# RoBeast_Power_Switching.net
KiCad netlist of a schematic drawn in Altium Designer
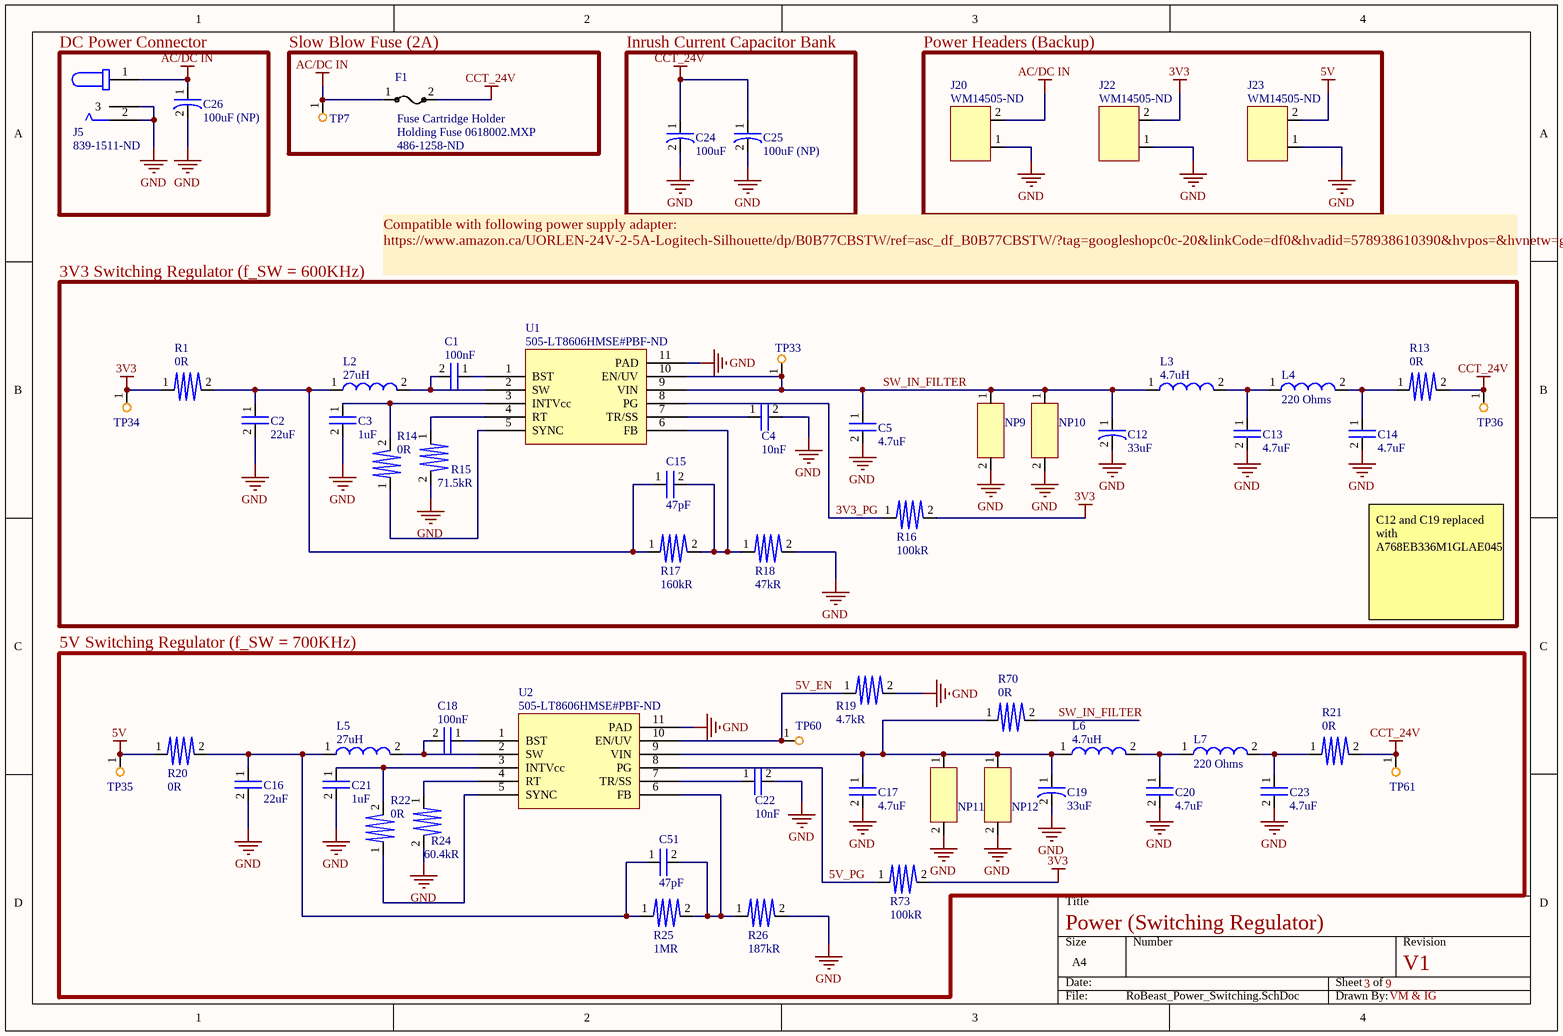
[diagram p0: RoBeast_Power_Switching.SchDoc]

(export (version "E")
  (design (tool "Eeschema 10.0.6"))
  (components
    (comp (ref "C1")
      (value "100nF")
      (footprint "0805")
      (fields
        (field (name "MANUFACTURER") "KEMET")
        (field (name "MANUFACTURER PART NUMBER") "C0805C104J5RACTU")
      )
      (libsource (lib "RoBeast_Schematic_Library") (part "C0805C104J5RAC7800"))
    )
    (comp (ref "C2")
      (value "22uF")
      (footprint "1206")
      (fields
        (field (name "MANUFACTURER") "Samsung")
        (field (name "MANUFACTURER PART NUMBER") "CL31B226MPHNNNE")
      )
      (libsource (lib "RoBeast_Schematic_Library") (part "CL31B226MPHNNNE"))
    )
    (comp (ref "C3")
      (value "1uF")
      (footprint "0805")
      (fields
        (field (name "MANUFACTURER") "Yageo")
        (field (name "MANUFACTURER PART NUMBER") "CC0805JKX7R9BB105")
      )
      (libsource (lib "RoBeast_Schematic_Library") (part "CC0805JKX7R9BB105"))
    )
    (comp (ref "C4")
      (value "10nF")
      (footprint "0805")
      (fields
        (field (name "MANUFACTURER") "KEMET")
        (field (name "MANUFACTURER PART NUMBER") "C0805C103J5RAC7210")
      )
      (libsource (lib "RoBeast_Schematic_Library") (part "C0805C103J5RAC7210"))
    )
    (comp (ref "C5")
      (value "4.7uF")
      (footprint "1206")
      (fields
        (field (name "MANUFACTURER") "KEMET")
        (field (name "MANUFACTURER PART NUMBER") "C1206C475K5RACAUTO")
      )
      (libsource (lib "RoBeast_Schematic_Library") (part "C1206C475K5RACAUTO"))
    )
    (comp (ref "C12")
      (value "33uF")
      (footprint "63SXV33M")
      (fields (field (name "MANUFACTURER") "Panasonic") (field (name "MANUFACTURER PART NUMBER") "63SXV33M"))
      (libsource (lib "RoBeast_Schematic_Library") (part "63SXV33M"))
    )
    (comp (ref "C13")
      (value "4.7uF")
      (footprint "1206")
      (fields
        (field (name "MANUFACTURER") "KEMET")
        (field (name "MANUFACTURER PART NUMBER") "C1206C475K5RACAUTO")
      )
      (libsource (lib "RoBeast_Schematic_Library") (part "C1206C475K5RACAUTO"))
    )
    (comp (ref "C14")
      (value "4.7uF")
      (footprint "1206")
      (fields
        (field (name "MANUFACTURER") "KEMET")
        (field (name "MANUFACTURER PART NUMBER") "C1206C475K5RACAUTO")
      )
      (libsource (lib "RoBeast_Schematic_Library") (part "C1206C475K5RACAUTO"))
    )
    (comp (ref "C15")
      (value "47pF")
      (footprint "0805")
      (fields
        (field (name "MANUFACTURER") "KEMET")
        (field (name "MANUFACTURER PART NUMBER") "C0805C470J5GAC7210")
      )
      (libsource (lib "RoBeast_Schematic_Library") (part "C0805C470J5GAC7210"))
    )
    (comp (ref "C16")
      (value "22uF")
      (footprint "1206")
      (fields
        (field (name "MANUFACTURER") "Samsung")
        (field (name "MANUFACTURER PART NUMBER") "CL31B226MPHNNNE")
      )
      (libsource (lib "RoBeast_Schematic_Library") (part "CL31B226MPHNNNE"))
    )
    (comp (ref "C17")
      (value "4.7uF")
      (footprint "1206")
      (fields
        (field (name "MANUFACTURER") "KEMET")
        (field (name "MANUFACTURER PART NUMBER") "C1206C475K5RACAUTO")
      )
      (libsource (lib "RoBeast_Schematic_Library") (part "C1206C475K5RACAUTO"))
    )
    (comp (ref "C18")
      (value "100nF")
      (footprint "0805")
      (fields
        (field (name "MANUFACTURER") "KEMET")
        (field (name "MANUFACTURER PART NUMBER") "C0805C104J5RACTU")
      )
      (libsource (lib "RoBeast_Schematic_Library") (part "C0805C104J5RAC7800"))
    )
    (comp (ref "C19")
      (value "33uF")
      (footprint "63SXV33M")
      (fields (field (name "MANUFACTURER") "Panasonic") (field (name "MANUFACTURER PART NUMBER") "63SXV33M"))
      (libsource (lib "RoBeast_Schematic_Library") (part "63SXV33M"))
    )
    (comp (ref "C20")
      (value "4.7uF")
      (footprint "1206")
      (fields
        (field (name "MANUFACTURER") "KEMET")
        (field (name "MANUFACTURER PART NUMBER") "C1206C475K5RACAUTO")
      )
      (libsource (lib "RoBeast_Schematic_Library") (part "C1206C475K5RACAUTO"))
    )
    (comp (ref "C21")
      (value "1uF")
      (footprint "0805")
      (fields
        (field (name "MANUFACTURER") "Yageo")
        (field (name "MANUFACTURER PART NUMBER") "CC0805JKX7R9BB105")
      )
      (libsource (lib "RoBeast_Schematic_Library") (part "CC0805JKX7R9BB105"))
    )
    (comp (ref "C22")
      (value "10nF")
      (footprint "0805")
      (fields
        (field (name "MANUFACTURER") "KEMET")
        (field (name "MANUFACTURER PART NUMBER") "C0805C103J5RAC7210")
      )
      (libsource (lib "RoBeast_Schematic_Library") (part "C0805C103J5RAC7210"))
    )
    (comp (ref "C23")
      (value "4.7uF")
      (footprint "1206")
      (fields
        (field (name "MANUFACTURER") "KEMET")
        (field (name "MANUFACTURER PART NUMBER") "C1206C475K5RACAUTO")
      )
      (libsource (lib "RoBeast_Schematic_Library") (part "C1206C475K5RACAUTO"))
    )
    (comp (ref "C24")
      (value "100uF")
      (footprint "UCD1H101MNL1GS")
      (fields
        (field (name "MANUFACTURER") "Nichicon")
        (field (name "MANUFACTURER PART NUMBER") "UCD1H101MNL1GS")
      )
      (libsource (lib "RoBeast_Schematic_Library") (part "UCD1H101MNL1GS"))
    )
    (comp (ref "C25")
      (value "100uF (NP)")
      (footprint "UCD1H101MNL1GS")
      (fields
        (field (name "MANUFACTURER") "Nichicon")
        (field (name "MANUFACTURER PART NUMBER") "UCD1H101MNL1GS")
      )
      (libsource (lib "RoBeast_Schematic_Library") (part "UCD1H101MNL1GS"))
    )
    (comp (ref "C26")
      (value "100uF (NP)")
      (footprint "UCD1H101MNL1GS")
      (fields
        (field (name "MANUFACTURER") "Nichicon")
        (field (name "MANUFACTURER PART NUMBER") "UCD1H101MNL1GS")
      )
      (libsource (lib "RoBeast_Schematic_Library") (part "UCD1H101MNL1GS"))
    )
    (comp (ref "C51")
      (value "47pF")
      (footprint "0805")
      (fields
        (field (name "MANUFACTURER") "KEMET")
        (field (name "MANUFACTURER PART NUMBER") "C0805C470J5GAC7210")
      )
      (libsource (lib "RoBeast_Schematic_Library") (part "C0805C470J5GAC7210"))
    )
    (comp (ref "F1")
      (value "Fuse Cartridge Holder")
      (footprint "0031.8201")
      (description "Fuse Holder Open Design; 5 x 20mm; 500V; 10A; 1P; Solder THT 22.5mm")
      (fields
        (field (name "MANUFACTURER") "Schurter")
        (field (name "MANUFACTURER PART NUMBER") "00318201")
        (field (name "SUPPLIER PART NUMBER 1") "486-1258-ND")
      )
      (libsource (lib "RoBeast_Schematic_Library") (part "0031.8201"))
    )
    (comp (ref "J5")
      (value "Power Jack Connector")
      (footprint "54-00128")
      (description "Conn DC Power RCP 2 POS Solder RA Thru-Hole 3 Terminal 1 Port")
      (fields
        (field (name "MANUFACTURER") "Tensility")
        (field (name "MANUFACTURER PART NUMBER") "54-00128")
        (field (name "SUPPLIER PART NUMBER 1") "839-1511-ND")
      )
      (libsource (lib "RoBeast_Schematic_Library") (part "54-00128"))
    )
    (comp (ref "J20")
      (value "2 Pin Connector")
      (footprint "WM14505-ND")
      (description "Board Connector, 2 Contact(s), 2 Row(s), Male, Right Angle, Solder Terminal")
      (fields
        (field (name "MANUFACTURER") "Molex")
        (field (name "MANUFACTURER PART NUMBER") "0026013114")
        (field (name "SUPPLIER PART NUMBER 1") "WM14505-ND")
      )
      (libsource (lib "RoBeast_Schematic_Library") (part "WM14505-ND"))
    )
    (comp (ref "J22")
      (value "2 Pin Connector")
      (footprint "WM14505-ND")
      (description "Board Connector, 2 Contact(s), 2 Row(s), Male, Right Angle, Solder Terminal")
      (fields
        (field (name "MANUFACTURER") "Molex")
        (field (name "MANUFACTURER PART NUMBER") "0026013114")
        (field (name "SUPPLIER PART NUMBER 1") "WM14505-ND")
      )
      (libsource (lib "RoBeast_Schematic_Library") (part "WM14505-ND"))
    )
    (comp (ref "J23")
      (value "2 Pin Connector")
      (footprint "WM14505-ND")
      (description "Board Connector, 2 Contact(s), 2 Row(s), Male, Right Angle, Solder Terminal")
      (fields
        (field (name "MANUFACTURER") "Molex")
        (field (name "MANUFACTURER PART NUMBER") "0026013114")
        (field (name "SUPPLIER PART NUMBER 1") "WM14505-ND")
      )
      (libsource (lib "RoBeast_Schematic_Library") (part "WM14505-ND"))
    )
    (comp (ref "L2")
      (value "27uH")
      (footprint "MSS5121-273MLB")
      (description "General Purpose Inductor, 27uH, 20%, 1 Element, Ferrite-Core, SMD, 2020")
      (fields
        (field (name "MANUFACTURER") "Coilcraft")
        (field (name "MANUFACTURER PART NUMBER") "MSS5121-273MLB")
      )
      (libsource (lib "RoBeast_Schematic_Library") (part "MSS5121-273MLB"))
    )
    (comp (ref "L3")
      (value "4.7uH")
      (footprint "XAL4030-472MEC")
      (description "General Purpose Inductor, 4.7uH, 20%, 1 Element, Composite-Core, SMD, 1616")
      (fields
        (field (name "MANUFACTURER") "Coilcraft")
        (field (name "MANUFACTURER PART NUMBER") "XAL4030-472MEC")
      )
      (libsource (lib "RoBeast_Schematic_Library") (part "XAL4030-472MEC"))
    )
    (comp (ref "L4")
      (value "220 Ohms")
      (footprint "0805")
      (description "Ferrite Chip, 1 Function(s), 3A")
      (fields
        (field (name "MANUFACTURER") "TDK")
        (field (name "MANUFACTURER PART NUMBER") "MPZ2012S221AT000")
      )
      (libsource (lib "RoBeast_Schematic_Library") (part "MPZ2012S221AT000"))
    )
    (comp (ref "L5")
      (value "27uH")
      (footprint "MSS5121-273MLB")
      (description "General Purpose Inductor, 27uH, 20%, 1 Element, Ferrite-Core, SMD, 2020")
      (fields
        (field (name "MANUFACTURER") "Coilcraft")
        (field (name "MANUFACTURER PART NUMBER") "MSS5121-273MLB")
      )
      (libsource (lib "RoBeast_Schematic_Library") (part "MSS5121-273MLB"))
    )
    (comp (ref "L6")
      (value "4.7uH")
      (footprint "XAL4030-472MEC")
      (description "General Purpose Inductor, 4.7uH, 20%, 1 Element, Composite-Core, SMD, 1616")
      (fields
        (field (name "MANUFACTURER") "Coilcraft")
        (field (name "MANUFACTURER PART NUMBER") "XAL4030-472MEC")
      )
      (libsource (lib "RoBeast_Schematic_Library") (part "XAL4030-472MEC"))
    )
    (comp (ref "L7")
      (value "220 Ohms")
      (footprint "0805")
      (description "Ferrite Chip, 1 Function(s), 3A")
      (fields
        (field (name "MANUFACTURER") "TDK")
        (field (name "MANUFACTURER PART NUMBER") "MPZ2012S221AT000")
      )
      (libsource (lib "RoBeast_Schematic_Library") (part "MPZ2012S221AT000"))
    )
    (comp (ref "NP9")
      (value "Not Populated")
      (footprint "0805")
      (libsource (lib "RoBeast_Schematic_Library") (part "NP"))
    )
    (comp (ref "NP10")
      (value "Not Populated")
      (footprint "0805")
      (libsource (lib "RoBeast_Schematic_Library") (part "NP"))
    )
    (comp (ref "NP11")
      (value "Not Populated")
      (footprint "0805")
      (libsource (lib "RoBeast_Schematic_Library") (part "NP"))
    )
    (comp (ref "NP12")
      (value "Not Populated")
      (footprint "0805")
      (libsource (lib "RoBeast_Schematic_Library") (part "NP"))
    )
    (comp (ref "R1")
      (value "0R")
      (footprint "0805")
      (description "Fixed Resistor, Metal Glaze/thick Film, 0.125W, 0ohm, Surface Mount, 0805")
      (fields
        (field (name "MANUFACTURER") "Stackpole Electronics")
        (field (name "MANUFACTURER PART NUMBER") "RMCF0805ZT0R00")
      )
      (libsource (lib "RoBeast_Schematic_Library") (part "RMCF0805ZT0R00"))
    )
    (comp (ref "R13")
      (value "0R")
      (footprint "0805")
      (description "Fixed Resistor, Metal Glaze/thick Film, 0.125W, 0ohm, Surface Mount, 0805")
      (fields
        (field (name "MANUFACTURER") "Stackpole Electronics")
        (field (name "MANUFACTURER PART NUMBER") "RMCF0805ZT0R00")
      )
      (libsource (lib "RoBeast_Schematic_Library") (part "RMCF0805ZT0R00"))
    )
    (comp (ref "R14")
      (value "0R")
      (footprint "0805")
      (description "Fixed Resistor, Metal Glaze/thick Film, 0.125W, 0ohm, Surface Mount, 0805")
      (fields
        (field (name "MANUFACTURER") "Stackpole Electronics")
        (field (name "MANUFACTURER PART NUMBER") "RMCF0805ZT0R00")
      )
      (libsource (lib "RoBeast_Schematic_Library") (part "RMCF0805ZT0R00"))
    )
    (comp (ref "R15")
      (value "71.5kR")
      (footprint "0805")
      (fields
        (field (name "MANUFACTURER") "KOA Speer")
        (field (name "MANUFACTURER PART NUMBER") "RK73H2ATTD7152F")
        (field (name "TOLERANCE") "1%")
      )
      (libsource (lib "RoBeast_Schematic_Library") (part "RK73H2ATTD7152F"))
    )
    (comp (ref "R16")
      (value "100kR")
      (footprint "0805")
      (fields
        (field (name "MANUFACTURER") "Vishay")
        (field (name "MANUFACTURER PART NUMBER") "CRCW0805100KFKEAHP")
        (field (name "TOLERANCE") "1%")
      )
      (libsource (lib "RoBeast_Schematic_Library") (part "CRCW0805100KFKEAHP"))
    )
    (comp (ref "R17")
      (value "160kR")
      (footprint "0805")
      (fields
        (field (name "MANUFACTURER") "Yageo")
        (field (name "MANUFACTURER PART NUMBER") "RC0805FR-07160KL")
        (field (name "TOLERANCE") "1%")
      )
      (libsource (lib "RoBeast_Schematic_Library") (part "RC0805FR-07160KL"))
    )
    (comp (ref "R18")
      (value "47kR")
      (footprint "0805")
      (fields
        (field (name "MANUFACTURER") "Walsin Technologies")
        (field (name "MANUFACTURER PART NUMBER") "WR08X4702FTL")
        (field (name "TOLERANCE") "1%")
      )
      (libsource (lib "RoBeast_Schematic_Library") (part "WR08X4702FTL"))
    )
    (comp (ref "R19")
      (value "4.7kR")
      (footprint "0805")
      (fields
        (field (name "MANUFACTURER") "Vishay Dale")
        (field (name "MANUFACTURER PART NUMBER") "RCC08054K70FKEA")
      )
      (libsource (lib "RoBeast_Schematic_Library") (part "RCC08054K70FKEA"))
    )
    (comp (ref "R20")
      (value "0R")
      (footprint "0805")
      (description "Fixed Resistor, Metal Glaze/thick Film, 0.125W, 0ohm, Surface Mount, 0805")
      (fields
        (field (name "MANUFACTURER") "Stackpole Electronics")
        (field (name "MANUFACTURER PART NUMBER") "RMCF0805ZT0R00")
      )
      (libsource (lib "RoBeast_Schematic_Library") (part "RMCF0805ZT0R00"))
    )
    (comp (ref "R21")
      (value "0R")
      (footprint "0805")
      (description "Fixed Resistor, Metal Glaze/thick Film, 0.125W, 0ohm, Surface Mount, 0805")
      (fields
        (field (name "MANUFACTURER") "Stackpole Electronics")
        (field (name "MANUFACTURER PART NUMBER") "RMCF0805ZT0R00")
      )
      (libsource (lib "RoBeast_Schematic_Library") (part "RMCF0805ZT0R00"))
    )
    (comp (ref "R22")
      (value "0R")
      (footprint "0805")
      (description "Fixed Resistor, Metal Glaze/thick Film, 0.125W, 0ohm, Surface Mount, 0805")
      (fields
        (field (name "MANUFACTURER") "Stackpole Electronics")
        (field (name "MANUFACTURER PART NUMBER") "RMCF0805ZT0R00")
      )
      (libsource (lib "RoBeast_Schematic_Library") (part "RMCF0805ZT0R00"))
    )
    (comp (ref "R24")
      (value "60.4kR")
      (footprint "0805")
      (fields
        (field (name "MANUFACTURER") "Vishay")
        (field (name "MANUFACTURER PART NUMBER") "CRCW080560K4FKEA")
        (field (name "TOLERANCE") "1%")
      )
      (libsource (lib "RoBeast_Schematic_Library") (part "CRCW080560K4FKEA"))
    )
    (comp (ref "R25")
      (value "1MR")
      (footprint "0805")
      (fields
        (field (name "MANUFACTURER") "Yageo")
        (field (name "MANUFACTURER PART NUMBER") "RC0805FR-131ML")
        (field (name "TOLERANCE") "1%")
      )
      (libsource (lib "RoBeast_Schematic_Library") (part "RC0805FR-131ML"))
    )
    (comp (ref "R26")
      (value "187kR")
      (footprint "0805")
      (description "Fixed Resistor, Thin Film, 0.125W, 187000ohm, 150V, 0.1% +/-Tol, 25ppm/Cel, Surface Mount, 0805")
      (fields
        (field (name "MANUFACTURER") "Yageo")
        (field (name "MANUFACTURER PART NUMBER") "RT0805BRD07187KL")
      )
      (libsource (lib "RoBeast_Schematic_Library") (part "RT0805BRD07187KL"))
    )
    (comp (ref "R70")
      (value "0R")
      (footprint "0805")
      (description "Fixed Resistor, Metal Glaze/thick Film, 0.125W, 0ohm, Surface Mount, 0805")
      (fields
        (field (name "MANUFACTURER") "Stackpole Electronics")
        (field (name "MANUFACTURER PART NUMBER") "RMCF0805ZT0R00")
      )
      (libsource (lib "RoBeast_Schematic_Library") (part "RMCF0805ZT0R00"))
    )
    (comp (ref "R73")
      (value "100kR")
      (footprint "0805")
      (fields
        (field (name "MANUFACTURER") "Vishay")
        (field (name "MANUFACTURER PART NUMBER") "CRCW0805100KFKEAHP")
        (field (name "TOLERANCE") "1%")
      )
      (libsource (lib "RoBeast_Schematic_Library") (part "CRCW0805100KFKEAHP"))
    )
    (comp (ref "TP7")
      (value "Test Point")
      (footprint "Test Point")
      (libsource (lib "RoBeast_Schematic_Library") (part "Test Point"))
    )
    (comp (ref "TP33")
      (value "Test Point")
      (footprint "Test Point")
      (libsource (lib "RoBeast_Schematic_Library") (part "Test Point"))
    )
    (comp (ref "TP34")
      (value "Test Point")
      (footprint "Test Point")
      (libsource (lib "RoBeast_Schematic_Library") (part "Test Point"))
    )
    (comp (ref "TP35")
      (value "Test Point")
      (footprint "Test Point")
      (libsource (lib "RoBeast_Schematic_Library") (part "Test Point"))
    )
    (comp (ref "TP36")
      (value "Test Point")
      (footprint "Test Point")
      (libsource (lib "RoBeast_Schematic_Library") (part "Test Point"))
    )
    (comp (ref "TP60")
      (value "Test Point")
      (footprint "Test Point")
      (libsource (lib "RoBeast_Schematic_Library") (part "Test Point"))
    )
    (comp (ref "TP61")
      (value "Test Point")
      (footprint "Test Point")
      (libsource (lib "RoBeast_Schematic_Library") (part "Test Point"))
    )
    (comp (ref "U1")
      (value "Switching Regulator")
      (footprint "LT8606HMSE#PBF")
      (fields
        (field (name "MANUFACTURER") "Analog Devices")
        (field (name "MANUFACTURER PART NUMBER") "LT8606HMSE#PBF")
        (field (name "SUPPLIER PART NUMBER 1") "505-LT8606HMSE#PBF-ND")
      )
      (libsource (lib "RoBeast_Schematic_Library") (part "LT8606HMSE#PBF"))
    )
    (comp (ref "U2")
      (value "Switching Regulator")
      (footprint "LT8606HMSE#PBF")
      (fields
        (field (name "MANUFACTURER") "Analog Devices")
        (field (name "MANUFACTURER PART NUMBER") "LT8606HMSE#PBF")
        (field (name "SUPPLIER PART NUMBER 1") "505-LT8606HMSE#PBF-ND")
      )
      (libsource (lib "RoBeast_Schematic_Library") (part "LT8606HMSE#PBF"))
    )
  )
  (nets
    (net (code "1") (name "/3V3_PG") (class "Default")
      (node (ref "R16") (pin "1") (pinfunction "1_1") (pintype "passive"))
      (node (ref "U1") (pin "8") (pinfunction "PG_8") (pintype "passive"))
    )
    (net (code "2") (name "/5V_EN") (class "Default")
      (node (ref "R19") (pin "1") (pinfunction "1_1") (pintype "passive"))
      (node (ref "TP60") (pin "1") (pinfunction "1_1") (pintype "passive"))
      (node (ref "U2") (pin "10") (pinfunction "EN/UV_10") (pintype "passive"))
    )
    (net (code "3") (name "/5V_PG") (class "Default")
      (node (ref "R73") (pin "1") (pinfunction "1_1") (pintype "passive"))
      (node (ref "U2") (pin "8") (pinfunction "PG_8") (pintype "passive"))
    )
    (net (code "4") (name "/SW_IN_FILTER") (class "Default")
      (node (ref "C12") (pin "1") (pinfunction "1_1") (pintype "passive"))
      (node (ref "C5") (pin "1") (pinfunction "1_1") (pintype "passive"))
      (node (ref "L3") (pin "1") (pinfunction "1_1") (pintype "passive"))
      (node (ref "NP10") (pin "1") (pinfunction "1_1") (pintype "passive"))
      (node (ref "NP9") (pin "1") (pinfunction "1_1") (pintype "passive"))
      (node (ref "R70") (pin "2") (pinfunction "2_2") (pintype "passive"))
      (node (ref "TP33") (pin "1") (pinfunction "1_1") (pintype "passive"))
      (node (ref "U1") (pin "10") (pinfunction "EN/UV_10") (pintype "passive"))
      (node (ref "U1") (pin "9") (pinfunction "VIN_9") (pintype "passive"))
    )
    (net (code "5") (name "3V3") (class "Default")
      (node (ref "J22") (pin "2") (pinfunction "2_2") (pintype "passive"))
      (node (ref "R1") (pin "1") (pinfunction "1_1") (pintype "passive"))
      (node (ref "R16") (pin "2") (pinfunction "2_2") (pintype "passive"))
      (node (ref "R73") (pin "2") (pinfunction "2_2") (pintype "passive"))
      (node (ref "TP34") (pin "1") (pinfunction "1_1") (pintype "passive"))
    )
    (net (code "6") (name "5V") (class "Default")
      (node (ref "J23") (pin "2") (pinfunction "2_2") (pintype "passive"))
      (node (ref "R20") (pin "1") (pinfunction "1_1") (pintype "passive"))
      (node (ref "TP35") (pin "1") (pinfunction "1_1") (pintype "passive"))
    )
    (net (code "7") (name "AC{slash}DC IN") (class "Default")
      (node (ref "C26") (pin "1") (pinfunction "1_1") (pintype "passive"))
      (node (ref "F1") (pin "1") (pinfunction "1_1") (pintype "passive"))
      (node (ref "J20") (pin "2") (pinfunction "2_2") (pintype "passive"))
      (node (ref "J5") (pin "1") (pinfunction "1_1") (pintype "passive"))
      (node (ref "TP7") (pin "1") (pinfunction "1_1") (pintype "passive"))
    )
    (net (code "8") (name "CCT_24V") (class "Default")
      (node (ref "C24") (pin "1") (pinfunction "1_1") (pintype "passive"))
      (node (ref "C25") (pin "1") (pinfunction "1_1") (pintype "passive"))
      (node (ref "F1") (pin "2") (pinfunction "2_2") (pintype "passive"))
      (node (ref "R13") (pin "2") (pinfunction "2_2") (pintype "passive"))
      (node (ref "R21") (pin "2") (pinfunction "2_2") (pintype "passive"))
      (node (ref "TP36") (pin "1") (pinfunction "1_1") (pintype "passive"))
      (node (ref "TP61") (pin "1") (pinfunction "1_1") (pintype "passive"))
    )
    (net (code "9") (name "GND") (class "Default")
      (node (ref "C12") (pin "2") (pinfunction "2_2") (pintype "passive"))
      (node (ref "C13") (pin "2") (pinfunction "2_2") (pintype "passive"))
      (node (ref "C14") (pin "2") (pinfunction "2_2") (pintype "passive"))
      (node (ref "C16") (pin "2") (pinfunction "2_2") (pintype "passive"))
      (node (ref "C17") (pin "2") (pinfunction "2_2") (pintype "passive"))
      (node (ref "C19") (pin "2") (pinfunction "2_2") (pintype "passive"))
      (node (ref "C2") (pin "2") (pinfunction "2_2") (pintype "passive"))
      (node (ref "C20") (pin "2") (pinfunction "2_2") (pintype "passive"))
      (node (ref "C21") (pin "2") (pinfunction "2_2") (pintype "passive"))
      (node (ref "C22") (pin "2") (pinfunction "2_2") (pintype "passive"))
      (node (ref "C23") (pin "2") (pinfunction "2_2") (pintype "passive"))
      (node (ref "C24") (pin "2") (pinfunction "2_2") (pintype "passive"))
      (node (ref "C25") (pin "2") (pinfunction "2_2") (pintype "passive"))
      (node (ref "C26") (pin "2") (pinfunction "2_2") (pintype "passive"))
      (node (ref "C3") (pin "2") (pinfunction "2_2") (pintype "passive"))
      (node (ref "C4") (pin "2") (pinfunction "2_2") (pintype "passive"))
      (node (ref "C5") (pin "2") (pinfunction "2_2") (pintype "passive"))
      (node (ref "J20") (pin "1") (pinfunction "1_1") (pintype "passive"))
      (node (ref "J22") (pin "1") (pinfunction "1_1") (pintype "passive"))
      (node (ref "J23") (pin "1") (pinfunction "1_1") (pintype "passive"))
      (node (ref "J5") (pin "2") (pinfunction "2_2") (pintype "passive"))
      (node (ref "J5") (pin "3") (pinfunction "3_3") (pintype "power_in"))
      (node (ref "NP10") (pin "2") (pinfunction "2_2") (pintype "passive"))
      (node (ref "NP11") (pin "2") (pinfunction "2_2") (pintype "passive"))
      (node (ref "NP12") (pin "2") (pinfunction "2_2") (pintype "passive"))
      (node (ref "NP9") (pin "2") (pinfunction "2_2") (pintype "passive"))
      (node (ref "R15") (pin "2") (pinfunction "2_2") (pintype "passive"))
      (node (ref "R18") (pin "2") (pinfunction "2_2") (pintype "passive"))
      (node (ref "R19") (pin "2") (pinfunction "2_2") (pintype "passive"))
      (node (ref "R24") (pin "2") (pinfunction "2_2") (pintype "passive"))
      (node (ref "R26") (pin "2") (pinfunction "2_2") (pintype "passive"))
      (node (ref "U1") (pin "11") (pinfunction "PAD_11") (pintype "passive"))
      (node (ref "U2") (pin "11") (pinfunction "PAD_11") (pintype "passive"))
    )
    (net (code "10") (name "Net-(C13-Pad1)") (class "Default")
      (node (ref "C13") (pin "1") (pinfunction "1_1") (pintype "passive"))
      (node (ref "L3") (pin "2") (pinfunction "2_2") (pintype "passive"))
      (node (ref "L4") (pin "1") (pinfunction "1_1") (pintype "passive"))
    )
    (net (code "11") (name "Net-(C14-Pad1)") (class "Default")
      (node (ref "C14") (pin "1") (pinfunction "1_1") (pintype "passive"))
      (node (ref "L4") (pin "2") (pinfunction "2_2") (pintype "passive"))
      (node (ref "R13") (pin "1") (pinfunction "1_1") (pintype "passive"))
    )
    (net (code "12") (name "Net-(C15-Pad1)") (class "Default")
      (node (ref "C15") (pin "1") (pinfunction "1_1") (pintype "passive"))
      (node (ref "C2") (pin "1") (pinfunction "1_1") (pintype "passive"))
      (node (ref "L2") (pin "1") (pinfunction "1_1") (pintype "passive"))
      (node (ref "R1") (pin "2") (pinfunction "2_2") (pintype "passive"))
      (node (ref "R17") (pin "1") (pinfunction "1_1") (pintype "passive"))
    )
    (net (code "13") (name "Net-(C16-Pad1)") (class "Default")
      (node (ref "C16") (pin "1") (pinfunction "1_1") (pintype "passive"))
      (node (ref "C51") (pin "1") (pinfunction "1_1") (pintype "passive"))
      (node (ref "L5") (pin "1") (pinfunction "1_1") (pintype "passive"))
      (node (ref "R20") (pin "2") (pinfunction "2_2") (pintype "passive"))
      (node (ref "R25") (pin "1") (pinfunction "1_1") (pintype "passive"))
    )
    (net (code "14") (name "Net-(C20-Pad1)") (class "Default")
      (node (ref "C20") (pin "1") (pinfunction "1_1") (pintype "passive"))
      (node (ref "L6") (pin "2") (pinfunction "2_2") (pintype "passive"))
      (node (ref "L7") (pin "1") (pinfunction "1_1") (pintype "passive"))
    )
    (net (code "15") (name "Net-(C23-Pad1)") (class "Default")
      (node (ref "C23") (pin "1") (pinfunction "1_1") (pintype "passive"))
      (node (ref "L7") (pin "2") (pinfunction "2_2") (pintype "passive"))
      (node (ref "R21") (pin "1") (pinfunction "1_1") (pintype "passive"))
    )
    (net (code "16") (name "Net-(U1-BST)") (class "Default")
      (node (ref "C1") (pin "1") (pinfunction "1_1") (pintype "passive"))
      (node (ref "U1") (pin "1") (pinfunction "BST_1") (pintype "passive"))
    )
    (net (code "17") (name "Net-(U1-FB)") (class "Default")
      (node (ref "C15") (pin "2") (pinfunction "2_2") (pintype "passive"))
      (node (ref "R17") (pin "2") (pinfunction "2_2") (pintype "passive"))
      (node (ref "R18") (pin "1") (pinfunction "1_1") (pintype "passive"))
      (node (ref "U1") (pin "6") (pinfunction "FB_6") (pintype "passive"))
    )
    (net (code "18") (name "Net-(U1-INTVcc)") (class "Default")
      (node (ref "C3") (pin "1") (pinfunction "1_1") (pintype "passive"))
      (node (ref "R14") (pin "2") (pinfunction "2_2") (pintype "passive"))
      (node (ref "U1") (pin "3") (pinfunction "INTVcc_3") (pintype "passive"))
    )
    (net (code "19") (name "Net-(U1-RT)") (class "Default")
      (node (ref "R15") (pin "1") (pinfunction "1_1") (pintype "passive"))
      (node (ref "U1") (pin "4") (pinfunction "RT_4") (pintype "passive"))
    )
    (net (code "20") (name "Net-(U1-SW)") (class "Default")
      (node (ref "C1") (pin "2") (pinfunction "2_2") (pintype "passive"))
      (node (ref "L2") (pin "2") (pinfunction "2_2") (pintype "passive"))
      (node (ref "U1") (pin "2") (pinfunction "SW_2") (pintype "passive"))
    )
    (net (code "21") (name "Net-(U1-SYNC)") (class "Default")
      (node (ref "R14") (pin "1") (pinfunction "1_1") (pintype "passive"))
      (node (ref "U1") (pin "5") (pinfunction "SYNC_5") (pintype "passive"))
    )
    (net (code "22") (name "Net-(U1-TR{slash}SS)") (class "Default")
      (node (ref "C4") (pin "1") (pinfunction "1_1") (pintype "passive"))
      (node (ref "U1") (pin "7") (pinfunction "TR/SS_7") (pintype "passive"))
    )
    (net (code "23") (name "Net-(U2-BST)") (class "Default")
      (node (ref "C18") (pin "1") (pinfunction "1_1") (pintype "passive"))
      (node (ref "U2") (pin "1") (pinfunction "BST_1") (pintype "passive"))
    )
    (net (code "24") (name "Net-(U2-FB)") (class "Default")
      (node (ref "C51") (pin "2") (pinfunction "2_2") (pintype "passive"))
      (node (ref "R25") (pin "2") (pinfunction "2_2") (pintype "passive"))
      (node (ref "R26") (pin "1") (pinfunction "1_1") (pintype "passive"))
      (node (ref "U2") (pin "6") (pinfunction "FB_6") (pintype "passive"))
    )
    (net (code "25") (name "Net-(U2-INTVcc)") (class "Default")
      (node (ref "C21") (pin "1") (pinfunction "1_1") (pintype "passive"))
      (node (ref "R22") (pin "2") (pinfunction "2_2") (pintype "passive"))
      (node (ref "U2") (pin "3") (pinfunction "INTVcc_3") (pintype "passive"))
    )
    (net (code "26") (name "Net-(U2-RT)") (class "Default")
      (node (ref "R24") (pin "1") (pinfunction "1_1") (pintype "passive"))
      (node (ref "U2") (pin "4") (pinfunction "RT_4") (pintype "passive"))
    )
    (net (code "27") (name "Net-(U2-SW)") (class "Default")
      (node (ref "C18") (pin "2") (pinfunction "2_2") (pintype "passive"))
      (node (ref "L5") (pin "2") (pinfunction "2_2") (pintype "passive"))
      (node (ref "U2") (pin "2") (pinfunction "SW_2") (pintype "passive"))
    )
    (net (code "28") (name "Net-(U2-SYNC)") (class "Default")
      (node (ref "R22") (pin "1") (pinfunction "1_1") (pintype "passive"))
      (node (ref "U2") (pin "5") (pinfunction "SYNC_5") (pintype "passive"))
    )
    (net (code "29") (name "Net-(U2-TR{slash}SS)") (class "Default")
      (node (ref "C22") (pin "1") (pinfunction "1_1") (pintype "passive"))
      (node (ref "U2") (pin "7") (pinfunction "TR/SS_7") (pintype "passive"))
    )
    (net (code "30") (name "Net-(U2-VIN)") (class "Default")
      (node (ref "C17") (pin "1") (pinfunction "1_1") (pintype "passive"))
      (node (ref "C19") (pin "1") (pinfunction "1_1") (pintype "passive"))
      (node (ref "L6") (pin "1") (pinfunction "1_1") (pintype "passive"))
      (node (ref "NP11") (pin "1") (pinfunction "1_1") (pintype "passive"))
      (node (ref "NP12") (pin "1") (pinfunction "1_1") (pintype "passive"))
      (node (ref "R70") (pin "1") (pinfunction "1_1") (pintype "passive"))
      (node (ref "U2") (pin "9") (pinfunction "VIN_9") (pintype "passive"))
    )
  )
)
